# 1030220084.net
KiCad netlist of a schematic drawn in Altium Designer
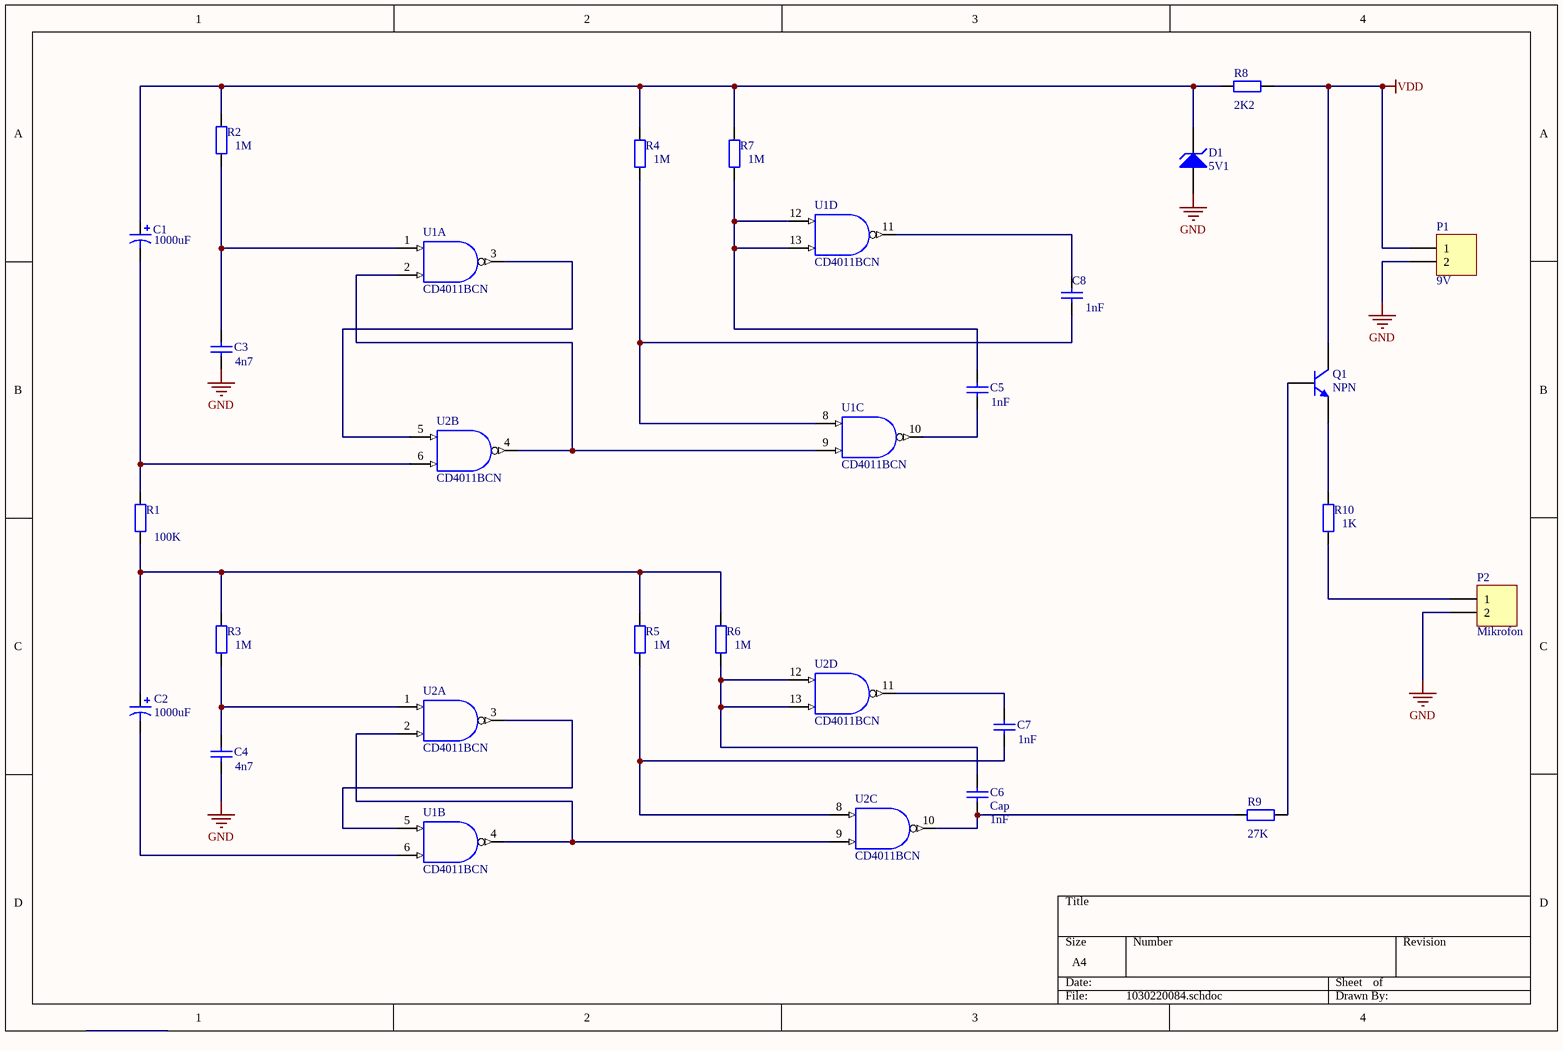
[diagram p0: 1030220084.schdoc]

(export (version "E")
  (design (tool "Eeschema 10.0.6"))
  (components
    (comp (ref "C1")
      (value "1000uF")
      (footprint "RB7.6-15")
      (description "Polarized Capacitor (Radial)")
      (fields (field (name "PUBLISHER") "Altium Limited"))
      (libsource (lib "Miscellaneous Devices") (part "Cap Pol1"))
    )
    (comp (ref "C2")
      (value "1000uF")
      (footprint "RB7.6-15")
      (description "Polarized Capacitor (Radial)")
      (fields (field (name "PUBLISHER") "Altium Limited"))
      (libsource (lib "Miscellaneous Devices") (part "Cap Pol1"))
    )
    (comp (ref "C3")
      (value "4n7")
      (footprint "RAD-0.3")
      (description "Capacitor")
      (fields (field (name "PUBLISHER") "Altium Limited"))
      (libsource (lib "Miscellaneous Devices") (part "Cap"))
    )
    (comp (ref "C4")
      (value "4n7")
      (footprint "RAD-0.3")
      (description "Capacitor")
      (fields (field (name "PUBLISHER") "Altium Limited"))
      (libsource (lib "Miscellaneous Devices") (part "Cap"))
    )
    (comp (ref "C5")
      (value "1nF")
      (footprint "RAD-0.3")
      (description "Capacitor")
      (fields (field (name "PUBLISHER") "Altium Limited"))
      (libsource (lib "Miscellaneous Devices") (part "Cap"))
    )
    (comp (ref "C6")
      (value "Cap")
      (footprint "RAD-0.3")
      (description "Capacitor")
      (fields (field (name "ALTIUM_VALUE") "1nF") (field (name "PUBLISHER") "Altium Limited"))
      (libsource (lib "Miscellaneous Devices") (part "Cap"))
    )
    (comp (ref "C7")
      (value "1nF")
      (footprint "RAD-0.3")
      (description "Capacitor")
      (fields (field (name "PUBLISHER") "Altium Limited"))
      (libsource (lib "Miscellaneous Devices") (part "Cap"))
    )
    (comp (ref "C8")
      (value "1nF")
      (footprint "RAD-0.3")
      (description "Capacitor")
      (fields (field (name "PUBLISHER") "Altium Limited"))
      (libsource (lib "Miscellaneous Devices") (part "Cap"))
    )
    (comp (ref "D1")
      (value "5V1")
      (footprint "DIODE-0.7")
      (description "Zener Diode")
      (fields (field (name "PUBLISHER") "Altium Limited"))
      (libsource (lib "Miscellaneous Devices") (part "D Zener"))
    )
    (comp (ref "P1")
      (value "9V")
      (footprint "HDR1X2")
      (fields (field (name "PUBLISHER") "Altium Limited"))
      (libsource (lib "Miscellaneous Connectors") (part "Header 2"))
    )
    (comp (ref "P2")
      (value "Mikrofon")
      (footprint "HDR1X2")
      (description "Header, 2-Pin")
      (fields (field (name "PUBLISHER") "Altium Limited"))
      (libsource (lib "Miscellaneous Connectors") (part "Header 2"))
    )
    (comp (ref "Q1")
      (value "NPN")
      (footprint "TO-226-AA")
      (description "NPN Bipolar Transistor")
      (fields (field (name "PUBLISHER") "Altium Limited"))
      (libsource (lib "Miscellaneous Devices") (part "NPN"))
    )
    (comp (ref "R1")
      (value "100K")
      (footprint "AXIAL-0.4")
      (description "Resistor")
      (fields (field (name "PUBLISHER") "Altium Limited"))
      (libsource (lib "Miscellaneous Devices") (part "Res2"))
    )
    (comp (ref "R2")
      (value "1M")
      (footprint "AXIAL-0.4")
      (description "Resistor")
      (fields (field (name "PUBLISHER") "Altium Limited"))
      (libsource (lib "Miscellaneous Devices") (part "Res2"))
    )
    (comp (ref "R3")
      (value "1M")
      (footprint "AXIAL-0.4")
      (description "Resistor")
      (fields (field (name "PUBLISHER") "Altium Limited"))
      (libsource (lib "Miscellaneous Devices") (part "Res2"))
    )
    (comp (ref "R4")
      (value "1M")
      (footprint "AXIAL-0.4")
      (description "Resistor")
      (fields (field (name "PUBLISHER") "Altium Limited"))
      (libsource (lib "Miscellaneous Devices") (part "Res2"))
    )
    (comp (ref "R5")
      (value "1M")
      (footprint "AXIAL-0.4")
      (description "Resistor")
      (fields (field (name "PUBLISHER") "Altium Limited"))
      (libsource (lib "Miscellaneous Devices") (part "Res2"))
    )
    (comp (ref "R6")
      (value "1M")
      (footprint "AXIAL-0.4")
      (description "Resistor")
      (fields (field (name "PUBLISHER") "Altium Limited"))
      (libsource (lib "Miscellaneous Devices") (part "Res2"))
    )
    (comp (ref "R7")
      (value "1M")
      (footprint "AXIAL-0.4")
      (description "Resistor")
      (fields (field (name "PUBLISHER") "Altium Limited"))
      (libsource (lib "Miscellaneous Devices") (part "Res2"))
    )
    (comp (ref "R8")
      (value "2K2")
      (footprint "AXIAL-0.4")
      (description "Resistor")
      (fields (field (name "PUBLISHER") "Altium Limited"))
      (libsource (lib "") (part "Res2_1"))
    )
    (comp (ref "R9")
      (value "27K")
      (footprint "AXIAL-0.4")
      (description "resistor")
      (fields (field (name "PUBLISHER") "Altium Limited"))
      (libsource (lib "") (part "Res2_1"))
    )
    (comp (ref "R10")
      (value "1K")
      (footprint "AXIAL-0.4")
      (description "Resistor")
      (fields (field (name "PUBLISHER") "Altium Limited"))
      (libsource (lib "Miscellaneous Devices") (part "Res2"))
    )
    (comp (ref "U1")
      (value "CD4011BCN")
      (footprint "N14A")
      (description "Quad 2-Input NAND Buffered B series Gate, 14-Pin PDIP")
      (fields (field (name "PUBLISHER") "Altium Limited"))
      (libsource (lib "FSC Logic Gate") (part "CD4011BCN"))
    )
    (comp (ref "U2")
      (value "CD4011BCN")
      (footprint "N14A")
      (description "Quad 2-Input NAND Buffered B series Gate, 14-Pin PDIP")
      (fields (field (name "PUBLISHER") "Altium Limited"))
      (libsource (lib "FSC Logic Gate") (part "CD4011BCN"))
    )
  )
  (nets
    (net (code "1") (name "GND") (class "Default")
      (node (ref "C3") (pin "2") (pinfunction "2_2") (pintype "passive"))
      (node (ref "C4") (pin "1") (pinfunction "1_1") (pintype "passive"))
      (node (ref "D1") (pin "1") (pinfunction "A_1") (pintype "passive"))
      (node (ref "P1") (pin "2") (pinfunction "2_2") (pintype "passive"))
      (node (ref "P2") (pin "2") (pinfunction "2_2") (pintype "passive"))
      (node (ref "U1") (pin "7") (pinfunction "GND_7") (pintype "power_in"))
      (node (ref "U2") (pin "7") (pinfunction "GND_7") (pintype "power_in"))
    )
    (net (code "2") (name "Net-(C2-Pad1)") (class "Default")
      (node (ref "C2") (pin "1") (pinfunction "1_1") (pintype "passive"))
      (node (ref "R1") (pin "1") (pinfunction "1_1") (pintype "passive"))
      (node (ref "R3") (pin "2") (pinfunction "2_2") (pintype "passive"))
      (node (ref "R5") (pin "2") (pinfunction "2_2") (pintype "passive"))
      (node (ref "R6") (pin "2") (pinfunction "2_2") (pintype "passive"))
    )
    (net (code "3") (name "Net-(D1-K)") (class "Default")
      (node (ref "C1") (pin "1") (pinfunction "1_1") (pintype "passive"))
      (node (ref "D1") (pin "2") (pinfunction "K_2") (pintype "passive"))
      (node (ref "R2") (pin "2") (pinfunction "2_2") (pintype "passive"))
      (node (ref "R4") (pin "2") (pinfunction "2_2") (pintype "passive"))
      (node (ref "R7") (pin "2") (pinfunction "2_2") (pintype "passive"))
      (node (ref "R8") (pin "1") (pinfunction "1_1") (pintype "passive"))
    )
    (net (code "4") (name "Net-(P2-Pad1)") (class "Default")
      (node (ref "P2") (pin "1") (pinfunction "1_1") (pintype "passive"))
      (node (ref "R10") (pin "1") (pinfunction "1_1") (pintype "passive"))
    )
    (net (code "5") (name "Net-(Q1-B)") (class "Default")
      (node (ref "Q1") (pin "2") (pinfunction "B_2") (pintype "passive"))
      (node (ref "R9") (pin "2") (pinfunction "2_2") (pintype "passive"))
    )
    (net (code "6") (name "Net-(Q1-E)") (class "Default")
      (node (ref "Q1") (pin "3") (pinfunction "E_3") (pintype "passive"))
      (node (ref "R10") (pin "2") (pinfunction "2_2") (pintype "passive"))
    )
    (net (code "7") (name "Net-(U1A-A)") (class "Default")
      (node (ref "C3") (pin "1") (pinfunction "1_1") (pintype "passive"))
      (node (ref "R2") (pin "1") (pinfunction "1_1") (pintype "passive"))
      (node (ref "U1") (pin "1") (pinfunction "A_1") (pintype "input"))
    )
    (net (code "8") (name "Net-(U1A-B)") (class "Default")
      (node (ref "U1") (pin "2") (pinfunction "B_2") (pintype "input"))
      (node (ref "U1") (pin "9") (pinfunction "F_9") (pintype "input"))
      (node (ref "U2") (pin "4") (pinfunction "J_4") (pintype "output"))
    )
    (net (code "9") (name "Net-(U1A-J)") (class "Default")
      (node (ref "U1") (pin "3") (pinfunction "J_3") (pintype "output"))
      (node (ref "U2") (pin "5") (pinfunction "A_5") (pintype "input"))
    )
    (net (code "10") (name "Net-(U1B-A)") (class "Default")
      (node (ref "U1") (pin "5") (pinfunction "A_5") (pintype "input"))
      (node (ref "U2") (pin "3") (pinfunction "J_3") (pintype "output"))
    )
    (net (code "11") (name "Net-(U1B-B)") (class "Default")
      (node (ref "C2") (pin "2") (pinfunction "2_2") (pintype "passive"))
      (node (ref "U1") (pin "6") (pinfunction "B_6") (pintype "input"))
    )
    (net (code "12") (name "Net-(U1B-J)") (class "Default")
      (node (ref "U1") (pin "4") (pinfunction "J_4") (pintype "output"))
      (node (ref "U2") (pin "2") (pinfunction "B_2") (pintype "input"))
      (node (ref "U2") (pin "9") (pinfunction "F_9") (pintype "input"))
    )
    (net (code "13") (name "Net-(U1C-A)") (class "Default")
      (node (ref "C8") (pin "1") (pinfunction "1_1") (pintype "passive"))
      (node (ref "R4") (pin "1") (pinfunction "1_1") (pintype "passive"))
      (node (ref "U1") (pin "8") (pinfunction "A_8") (pintype "input"))
    )
    (net (code "14") (name "Net-(U1C-J)") (class "Default")
      (node (ref "C5") (pin "1") (pinfunction "1_1") (pintype "passive"))
      (node (ref "U1") (pin "10") (pinfunction "J_10") (pintype "output"))
    )
    (net (code "15") (name "Net-(U1D-A)") (class "Default")
      (node (ref "C5") (pin "2") (pinfunction "2_2") (pintype "passive"))
      (node (ref "R7") (pin "1") (pinfunction "1_1") (pintype "passive"))
      (node (ref "U1") (pin "12") (pinfunction "A_12") (pintype "input"))
      (node (ref "U1") (pin "13") (pinfunction "B_13") (pintype "input"))
    )
    (net (code "16") (name "Net-(U1D-J)") (class "Default")
      (node (ref "C8") (pin "2") (pinfunction "2_2") (pintype "passive"))
      (node (ref "U1") (pin "11") (pinfunction "J_11") (pintype "output"))
    )
    (net (code "17") (name "Net-(U2A-A)") (class "Default")
      (node (ref "C4") (pin "2") (pinfunction "2_2") (pintype "passive"))
      (node (ref "R3") (pin "1") (pinfunction "1_1") (pintype "passive"))
      (node (ref "U2") (pin "1") (pinfunction "A_1") (pintype "input"))
    )
    (net (code "18") (name "Net-(U2B-B)") (class "Default")
      (node (ref "C1") (pin "2") (pinfunction "2_2") (pintype "passive"))
      (node (ref "R1") (pin "2") (pinfunction "2_2") (pintype "passive"))
      (node (ref "U2") (pin "6") (pinfunction "B_6") (pintype "input"))
    )
    (net (code "19") (name "Net-(U2C-A)") (class "Default")
      (node (ref "C7") (pin "1") (pinfunction "1_1") (pintype "passive"))
      (node (ref "R5") (pin "1") (pinfunction "1_1") (pintype "passive"))
      (node (ref "U2") (pin "8") (pinfunction "A_8") (pintype "input"))
    )
    (net (code "20") (name "Net-(U2C-J)") (class "Default")
      (node (ref "C6") (pin "1") (pinfunction "1_1") (pintype "passive"))
      (node (ref "R9") (pin "1") (pinfunction "1_1") (pintype "passive"))
      (node (ref "U2") (pin "10") (pinfunction "J_10") (pintype "output"))
    )
    (net (code "21") (name "Net-(U2D-A)") (class "Default")
      (node (ref "C6") (pin "2") (pinfunction "2_2") (pintype "passive"))
      (node (ref "R6") (pin "1") (pinfunction "1_1") (pintype "passive"))
      (node (ref "U2") (pin "12") (pinfunction "A_12") (pintype "input"))
      (node (ref "U2") (pin "13") (pinfunction "B_13") (pintype "input"))
    )
    (net (code "22") (name "Net-(U2D-J)") (class "Default")
      (node (ref "C7") (pin "2") (pinfunction "2_2") (pintype "passive"))
      (node (ref "U2") (pin "11") (pinfunction "J_11") (pintype "output"))
    )
    (net (code "23") (name "VDD") (class "Default")
      (node (ref "P1") (pin "1") (pinfunction "1_1") (pintype "passive"))
      (node (ref "Q1") (pin "1") (pinfunction "C_1") (pintype "passive"))
      (node (ref "R8") (pin "2") (pinfunction "2_2") (pintype "passive"))
      (node (ref "U1") (pin "14") (pinfunction "VDD_14") (pintype "power_in"))
      (node (ref "U2") (pin "14") (pinfunction "VDD_14") (pintype "power_in"))
    )
  )
)
